# RFToy.net
KiCad netlist of a schematic drawn in EAGLE
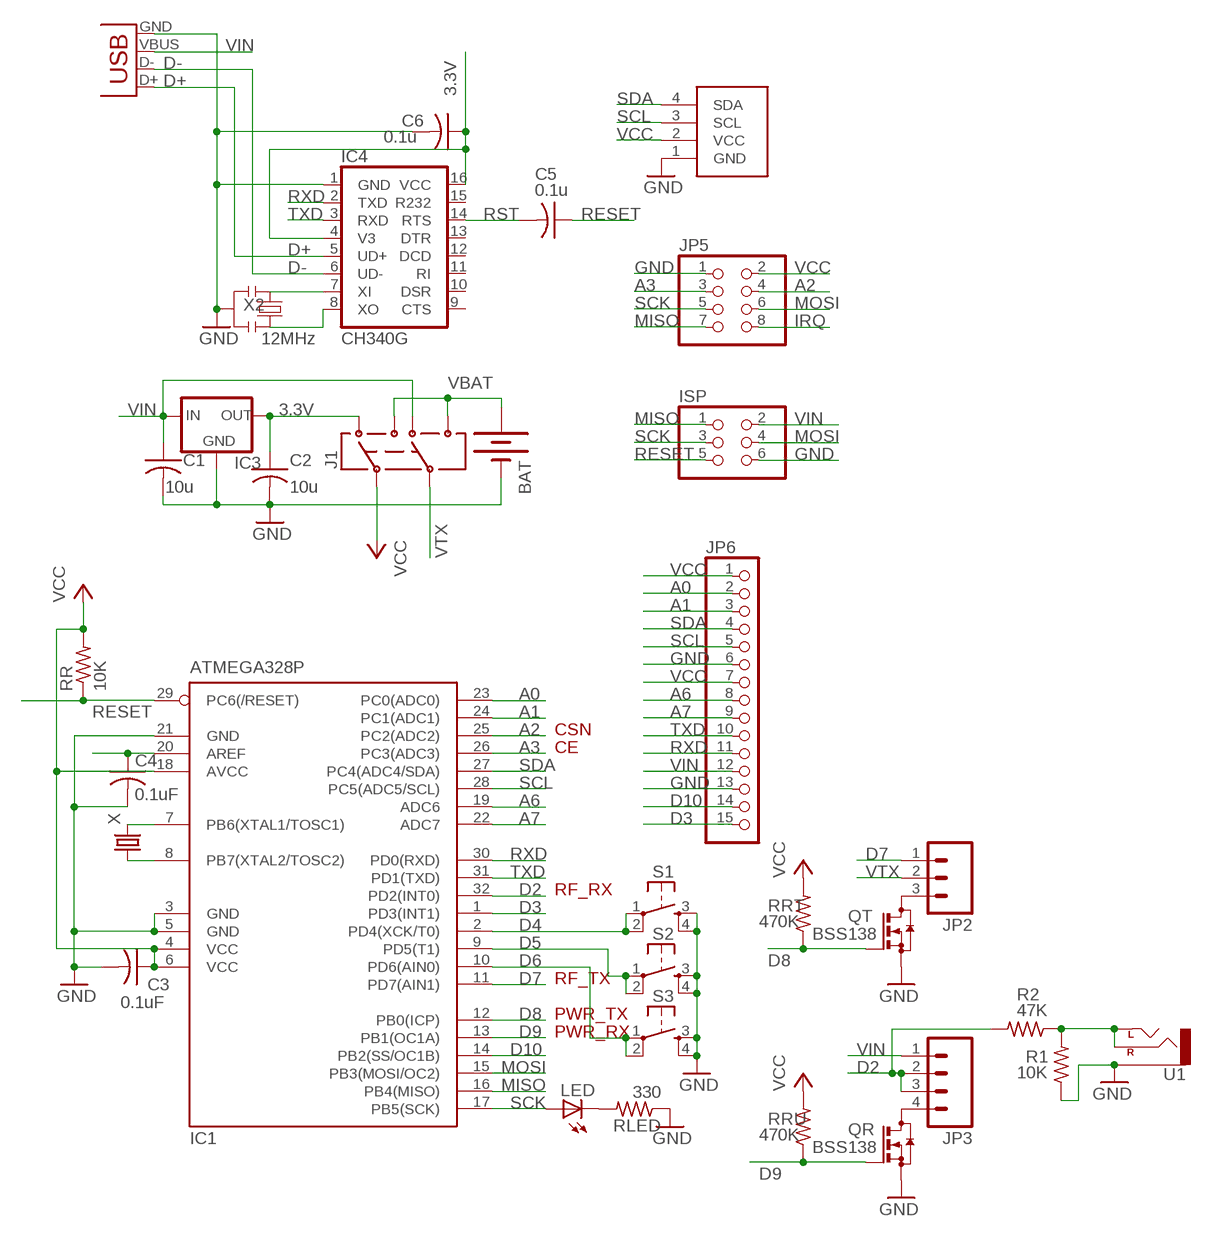
[diagram p0: schematic, sheet 1]

(export (version "E")
  (design (tool "Eeschema 10.0.6"))
  (components
    (comp (ref "BAT")
      (value "BATTERY20PTH")
      (footprint "eagle-import:BATTCOM_20MM_PTH")
      (libsource (lib "eagle-import") (part "BATTERY20PTH"))
    )
    (comp (ref "C1")
      (value "10u")
      (footprint "eagle-import:C0805K")
      (libsource (lib "eagle-import") (part "adafruit2013_C-USC0805K"))
    )
    (comp (ref "C2")
      (value "10u")
      (footprint "eagle-import:C0805K")
      (libsource (lib "eagle-import") (part "adafruit2013_C-USC0805K"))
    )
    (comp (ref "C3")
      (value "0.1uF")
      (footprint "eagle-import:C0805K")
      (libsource (lib "eagle-import") (part "adafruit2013_C-USC0805K"))
    )
    (comp (ref "C4")
      (value "0.1uF")
      (footprint "eagle-import:C0805K")
      (libsource (lib "eagle-import") (part "adafruit2013_C-USC0805K"))
    )
    (comp (ref "C5")
      (value "0.1u")
      (footprint "eagle-import:C0805K")
      (libsource (lib "eagle-import") (part "C-USC0805K"))
    )
    (comp (ref "C6")
      (value "0.1u")
      (footprint "eagle-import:C0805K")
      (libsource (lib "eagle-import") (part "C-USC0805K"))
    )
    (comp (ref "IC1")
      (value "ATMEGA328P")
      (footprint "eagle-import:TQFP32-08")
      (fields (field (name "MPN") "ATMEGA8-16AU"))
      (libsource (lib "eagle-import") (part "MEGA8-AI"))
    )
    (comp (ref "IC3")
      (value "MCP1700SOT233")
      (footprint "eagle-import:SOT23")
      (libsource (lib "eagle-import") (part "MCP1700SOT233"))
    )
    (comp (ref "IC4")
      (value "CH340G")
      (footprint "eagle-import:SO16")
      (libsource (lib "eagle-import") (part "CH340G"))
    )
    (comp (ref "ISP")
      (value "PINHD-2X3")
      (footprint "eagle-import:2X03")
      (libsource (lib "eagle-import") (part "PINHD-2X3"))
    )
    (comp (ref "J1")
      (value "AYZ0202")
      (footprint "eagle-import:AYZ0202")
      (libsource (lib "eagle-import") (part "AYZ0202"))
    )
    (comp (ref "JP2")
      (value "M03LOCK_LONGPADS")
      (footprint "eagle-import:1X03_LOCK_LONGPADS")
      (libsource (lib "eagle-import") (part "M03LOCK_LONGPADS"))
    )
    (comp (ref "JP3")
      (value "M04LOCK")
      (footprint "eagle-import:1X04_LOCK")
      (libsource (lib "eagle-import") (part "M04LOCK"))
    )
    (comp (ref "JP5")
      (value "PINHD-2X4")
      (footprint "eagle-import:2X04")
      (libsource (lib "eagle-import") (part "PINHD-2X4"))
    )
    (comp (ref "JP6")
      (value "PINHD-1X15-CB")
      (footprint "eagle-import:1X15-CB")
      (libsource (lib "eagle-import") (part "PINHD-1X15-CB"))
    )
    (comp (ref "LED")
      (value "LEDCHIPLED_0805")
      (footprint "eagle-import:CHIPLED_0805")
      (libsource (lib "eagle-import") (part "LEDCHIPLED_0805"))
    )
    (comp (ref "QR")
      (value "BSS138")
      (footprint "eagle-import:SOT23")
      (libsource (lib "eagle-import") (part "BSS123"))
    )
    (comp (ref "QT")
      (value "BSS138")
      (footprint "eagle-import:SOT23")
      (libsource (lib "eagle-import") (part "BSS123"))
    )
    (comp (ref "R1")
      (value "10K")
      (footprint "eagle-import:R0805")
      (libsource (lib "eagle-import") (part "R-US_R0805"))
    )
    (comp (ref "R2")
      (value "47K")
      (footprint "eagle-import:R0805")
      (libsource (lib "eagle-import") (part "R-US_R0805"))
    )
    (comp (ref "RLED")
      (value "330")
      (footprint "eagle-import:R0805")
      (libsource (lib "eagle-import") (part "R-US_R0805"))
    )
    (comp (ref "RR")
      (value "10K")
      (footprint "eagle-import:R0805")
      (libsource (lib "eagle-import") (part "R-US_R0805"))
    )
    (comp (ref "RRT")
      (value "470K")
      (footprint "eagle-import:R0805")
      (libsource (lib "eagle-import") (part "R-US_R0805"))
    )
    (comp (ref "RRU")
      (value "470K")
      (footprint "eagle-import:R0805")
      (libsource (lib "eagle-import") (part "R-US_R0805"))
    )
    (comp (ref "S1")
      (value "TAC_SWITCHPTH")
      (footprint "eagle-import:TACTILE-PTH")
      (libsource (lib "eagle-import") (part "TAC_SWITCHPTH"))
    )
    (comp (ref "S2")
      (value "TAC_SWITCHPTH")
      (footprint "eagle-import:TACTILE-PTH")
      (libsource (lib "eagle-import") (part "TAC_SWITCHPTH"))
    )
    (comp (ref "S3")
      (value "TAC_SWITCHPTH")
      (footprint "eagle-import:TACTILE-PTH")
      (libsource (lib "eagle-import") (part "TAC_SWITCHPTH"))
    )
    (comp (ref "U$1")
      (value "SSD1306_OLED_I2C")
      (footprint "eagle-import:SSD1306_OLED_I2C")
      (libsource (lib "eagle-import") (part "SSD1306_OLED_I2C"))
    )
    (comp (ref "U1")
      (value "AUDIO-JACKPTH")
      (footprint "eagle-import:AUDIO-JACK")
      (libsource (lib "eagle-import") (part "AUDIO-JACKPTH"))
    )
    (comp (ref "X")
      (value "CRYSTALTC26V")
      (footprint "eagle-import:TC26V")
      (libsource (lib "eagle-import") (part "CRYSTALTC26V"))
    )
    (comp (ref "X1")
      (value "USBSMD")
      (footprint "eagle-import:USB-MINIB")
      (libsource (lib "eagle-import") (part "USBSMD"))
    )
    (comp (ref "X2")
      (value "12MHz")
      (footprint "eagle-import:RESONATOR-SMD")
      (libsource (lib "eagle-import") (part "RESONATORSMD"))
    )
  )
  (nets
    (net (code "1") (name "/3.3V") (class "Default")
      (node (ref "C2") (pin "1") (pinfunction "1_1") (pintype "passive"))
      (node (ref "C6") (pin "1") (pinfunction "1_1") (pintype "passive"))
      (node (ref "IC3") (pin "2") (pinfunction "OUT_2") (pintype "passive"))
      (node (ref "IC4") (pin "16") (pinfunction "VCC_16") (pintype "power_in"))
      (node (ref "IC4") (pin "4") (pinfunction "V3_4") (pintype "bidirectional"))
      (node (ref "J1") (pin "3") (pinfunction "1_3") (pintype "bidirectional"))
    )
    (net (code "2") (name "/A0") (class "Default")
      (node (ref "IC1") (pin "23") (pinfunction "PC0(ADC0)_23") (pintype "bidirectional"))
      (node (ref "JP6") (pin "2") (pinfunction "2_2") (pintype "passive"))
    )
    (net (code "3") (name "/A1") (class "Default")
      (node (ref "IC1") (pin "24") (pinfunction "PC1(ADC1)_24") (pintype "bidirectional"))
      (node (ref "JP6") (pin "3") (pinfunction "3_3") (pintype "passive"))
    )
    (net (code "4") (name "/A2") (class "Default")
      (node (ref "IC1") (pin "25") (pinfunction "PC2(ADC2)_25") (pintype "bidirectional"))
      (node (ref "JP5") (pin "4") (pinfunction "4_4") (pintype "passive"))
    )
    (net (code "5") (name "/A3") (class "Default")
      (node (ref "IC1") (pin "26") (pinfunction "PC3(ADC3)_26") (pintype "bidirectional"))
      (node (ref "JP5") (pin "3") (pinfunction "3_3") (pintype "passive"))
    )
    (net (code "6") (name "/A6") (class "Default")
      (node (ref "IC1") (pin "19") (pinfunction "ADC6_19") (pintype "bidirectional"))
      (node (ref "JP6") (pin "8") (pinfunction "8_8") (pintype "passive"))
    )
    (net (code "7") (name "/A7") (class "Default")
      (node (ref "IC1") (pin "22") (pinfunction "ADC7_22") (pintype "bidirectional"))
      (node (ref "JP6") (pin "9") (pinfunction "9_9") (pintype "passive"))
    )
    (net (code "8") (name "/D+") (class "Default")
      (node (ref "IC4") (pin "5") (pinfunction "UD+_5") (pintype "bidirectional"))
      (node (ref "X1") (pin "D+") (pinfunction "D+_D+") (pintype "bidirectional"))
    )
    (net (code "9") (name "/D-") (class "Default")
      (node (ref "IC4") (pin "6") (pinfunction "UD-_6") (pintype "bidirectional"))
      (node (ref "X1") (pin "D-") (pinfunction "D-_D-") (pintype "bidirectional"))
    )
    (net (code "10") (name "/D2") (class "Default")
      (node (ref "IC1") (pin "32") (pinfunction "PD2(INT0)_32") (pintype "bidirectional"))
      (node (ref "JP3") (pin "2") (pinfunction "2_2") (pintype "passive"))
      (node (ref "JP3") (pin "3") (pinfunction "3_3") (pintype "passive"))
      (node (ref "R2") (pin "2") (pinfunction "2_2") (pintype "passive"))
    )
    (net (code "11") (name "/D3") (class "Default")
      (node (ref "IC1") (pin "1") (pinfunction "PD3(INT1)_1") (pintype "bidirectional"))
      (node (ref "JP6") (pin "15") (pinfunction "15_15") (pintype "passive"))
    )
    (net (code "12") (name "/D4") (class "Default")
      (node (ref "IC1") (pin "2") (pinfunction "PD4(XCK/T0)_2") (pintype "bidirectional"))
      (node (ref "S1") (pin "1") (pinfunction "1_1") (pintype "passive"))
      (node (ref "S1") (pin "2") (pinfunction "2_2") (pintype "passive"))
    )
    (net (code "13") (name "/D5") (class "Default")
      (node (ref "IC1") (pin "9") (pinfunction "PD5(T1)_9") (pintype "bidirectional"))
      (node (ref "S2") (pin "1") (pinfunction "1_1") (pintype "passive"))
      (node (ref "S2") (pin "2") (pinfunction "2_2") (pintype "passive"))
    )
    (net (code "14") (name "/D6") (class "Default")
      (node (ref "IC1") (pin "10") (pinfunction "PD6(AIN0)_10") (pintype "bidirectional"))
      (node (ref "S3") (pin "1") (pinfunction "1_1") (pintype "passive"))
      (node (ref "S3") (pin "2") (pinfunction "2_2") (pintype "passive"))
    )
    (net (code "15") (name "/D7") (class "Default")
      (node (ref "IC1") (pin "11") (pinfunction "PD7(AIN1)_11") (pintype "bidirectional"))
      (node (ref "JP2") (pin "1") (pinfunction "1_1") (pintype "passive"))
    )
    (net (code "16") (name "/D8") (class "Default")
      (node (ref "IC1") (pin "12") (pinfunction "PB0(ICP)_12") (pintype "bidirectional"))
      (node (ref "QT") (pin "1") (pinfunction "G_1") (pintype "passive"))
      (node (ref "RRT") (pin "1") (pinfunction "1_1") (pintype "passive"))
    )
    (net (code "17") (name "/D9") (class "Default")
      (node (ref "IC1") (pin "13") (pinfunction "PB1(OC1A)_13") (pintype "bidirectional"))
      (node (ref "QR") (pin "1") (pinfunction "G_1") (pintype "passive"))
      (node (ref "RRU") (pin "1") (pinfunction "1_1") (pintype "passive"))
    )
    (net (code "18") (name "/D10") (class "Default")
      (node (ref "IC1") (pin "14") (pinfunction "PB2(SS/OC1B)_14") (pintype "bidirectional"))
      (node (ref "JP6") (pin "14") (pinfunction "14_14") (pintype "passive"))
    )
    (net (code "19") (name "/IRQ") (class "Default")
      (node (ref "JP5") (pin "8") (pinfunction "8_8") (pintype "passive"))
    )
    (net (code "20") (name "/MISO") (class "Default")
      (node (ref "IC1") (pin "16") (pinfunction "PB4(MISO)_16") (pintype "bidirectional"))
      (node (ref "ISP") (pin "1") (pinfunction "1_1") (pintype "passive"))
      (node (ref "JP5") (pin "7") (pinfunction "7_7") (pintype "passive"))
    )
    (net (code "21") (name "/MOSI") (class "Default")
      (node (ref "IC1") (pin "15") (pinfunction "PB3(MOSI/OC2)_15") (pintype "bidirectional"))
      (node (ref "ISP") (pin "4") (pinfunction "4_4") (pintype "passive"))
      (node (ref "JP5") (pin "6") (pinfunction "6_6") (pintype "passive"))
    )
    (net (code "22") (name "/RESET") (class "Default")
      (node (ref "C5") (pin "1") (pinfunction "1_1") (pintype "passive"))
      (node (ref "IC1") (pin "29") (pinfunction "PC6(/RESET)_29") (pintype "bidirectional"))
      (node (ref "ISP") (pin "5") (pinfunction "5_5") (pintype "passive"))
      (node (ref "RR") (pin "1") (pinfunction "1_1") (pintype "passive"))
    )
    (net (code "23") (name "/RST") (class "Default")
      (node (ref "C5") (pin "2") (pinfunction "2_2") (pintype "passive"))
      (node (ref "IC4") (pin "14") (pinfunction "RTS_14") (pintype "bidirectional"))
    )
    (net (code "24") (name "/RXD") (class "Default")
      (node (ref "IC1") (pin "30") (pinfunction "PD0(RXD)_30") (pintype "bidirectional"))
      (node (ref "IC4") (pin "2") (pinfunction "TXD_2") (pintype "bidirectional"))
      (node (ref "JP6") (pin "11") (pinfunction "11_11") (pintype "passive"))
    )
    (net (code "25") (name "/SCK") (class "Default")
      (node (ref "IC1") (pin "17") (pinfunction "PB5(SCK)_17") (pintype "bidirectional"))
      (node (ref "ISP") (pin "3") (pinfunction "3_3") (pintype "passive"))
      (node (ref "JP5") (pin "5") (pinfunction "5_5") (pintype "passive"))
      (node (ref "LED") (pin "A") (pinfunction "A_A") (pintype "passive"))
    )
    (net (code "26") (name "/SCL") (class "Default")
      (node (ref "IC1") (pin "28") (pinfunction "PC5(ADC5/SCL)_28") (pintype "bidirectional"))
      (node (ref "JP6") (pin "5") (pinfunction "5_5") (pintype "passive"))
      (node (ref "U$1") (pin "3") (pinfunction "SCL_3") (pintype "bidirectional"))
    )
    (net (code "27") (name "/SDA") (class "Default")
      (node (ref "IC1") (pin "27") (pinfunction "PC4(ADC4/SDA)_27") (pintype "bidirectional"))
      (node (ref "JP6") (pin "4") (pinfunction "4_4") (pintype "passive"))
      (node (ref "U$1") (pin "4") (pinfunction "SDA_4") (pintype "bidirectional"))
    )
    (net (code "28") (name "/TXD") (class "Default")
      (node (ref "IC1") (pin "31") (pinfunction "PD1(TXD)_31") (pintype "bidirectional"))
      (node (ref "IC4") (pin "3") (pinfunction "RXD_3") (pintype "bidirectional"))
      (node (ref "JP6") (pin "10") (pinfunction "10_10") (pintype "passive"))
    )
    (net (code "29") (name "/VBAT") (class "Default")
      (node (ref "BAT") (pin "1") (pinfunction "+_1") (pintype "power_in"))
      (node (ref "J1") (pin "1") (pinfunction "3_1") (pintype "bidirectional"))
      (node (ref "J1") (pin "4") (pinfunction "6_4") (pintype "bidirectional"))
    )
    (net (code "30") (name "/VIN") (class "Default")
      (node (ref "C1") (pin "1") (pinfunction "1_1") (pintype "passive"))
      (node (ref "IC3") (pin "3") (pinfunction "IN_3") (pintype "input"))
      (node (ref "ISP") (pin "2") (pinfunction "2_2") (pintype "passive"))
      (node (ref "J1") (pin "6") (pinfunction "4_6") (pintype "bidirectional"))
      (node (ref "JP3") (pin "1") (pinfunction "1_1") (pintype "passive"))
      (node (ref "JP6") (pin "12") (pinfunction "12_12") (pintype "passive"))
      (node (ref "X1") (pin "VBUS") (pinfunction "VBUS_VBUS") (pintype "bidirectional"))
    )
    (net (code "31") (name "/VTX") (class "Default")
      (node (ref "J1") (pin "5") (pinfunction "5_5") (pintype "bidirectional"))
      (node (ref "JP2") (pin "2") (pinfunction "2_2") (pintype "passive"))
    )
    (net (code "32") (name "GND") (class "Default")
      (node (ref "BAT") (pin "2") (pinfunction "-_2") (pintype "power_in"))
      (node (ref "C1") (pin "2") (pinfunction "2_2") (pintype "passive"))
      (node (ref "C2") (pin "2") (pinfunction "2_2") (pintype "passive"))
      (node (ref "C3") (pin "2") (pinfunction "2_2") (pintype "passive"))
      (node (ref "C4") (pin "2") (pinfunction "2_2") (pintype "passive"))
      (node (ref "C6") (pin "2") (pinfunction "2_2") (pintype "passive"))
      (node (ref "IC1") (pin "21") (pinfunction "GND_21") (pintype "power_in"))
      (node (ref "IC1") (pin "3") (pinfunction "GND_3") (pintype "power_in"))
      (node (ref "IC1") (pin "5") (pinfunction "GND_5") (pintype "power_in"))
      (node (ref "IC3") (pin "1") (pinfunction "GND_1") (pintype "input"))
      (node (ref "IC4") (pin "1") (pinfunction "GND_1") (pintype "power_in"))
      (node (ref "ISP") (pin "6") (pinfunction "6_6") (pintype "passive"))
      (node (ref "JP5") (pin "1") (pinfunction "1_1") (pintype "passive"))
      (node (ref "JP6") (pin "13") (pinfunction "13_13") (pintype "passive"))
      (node (ref "JP6") (pin "6") (pinfunction "6_6") (pintype "passive"))
      (node (ref "QR") (pin "2") (pinfunction "S_2") (pintype "passive"))
      (node (ref "QT") (pin "2") (pinfunction "S_2") (pintype "passive"))
      (node (ref "R1") (pin "1") (pinfunction "1_1") (pintype "passive"))
      (node (ref "RLED") (pin "1") (pinfunction "1_1") (pintype "passive"))
      (node (ref "S1") (pin "3") (pinfunction "3_3") (pintype "passive"))
      (node (ref "S1") (pin "4") (pinfunction "4_4") (pintype "passive"))
      (node (ref "S2") (pin "3") (pinfunction "3_3") (pintype "passive"))
      (node (ref "S2") (pin "4") (pinfunction "4_4") (pintype "passive"))
      (node (ref "S3") (pin "3") (pinfunction "3_3") (pintype "passive"))
      (node (ref "S3") (pin "4") (pinfunction "4_4") (pintype "passive"))
      (node (ref "U$1") (pin "1") (pinfunction "GND_1") (pintype "power_in"))
      (node (ref "U1") (pin "SLEEVE") (pinfunction "SLEEVE_SLEEVE") (pintype "bidirectional"))
      (node (ref "X1") (pin "GND") (pinfunction "GND_GND") (pintype "bidirectional"))
      (node (ref "X2") (pin "2") (pinfunction "2_2") (pintype "passive"))
    )
    (net (code "33") (name "Net-(IC1-AREF)") (class "Default")
      (node (ref "C4") (pin "1") (pinfunction "1_1") (pintype "passive"))
      (node (ref "IC1") (pin "20") (pinfunction "AREF_20") (pintype "passive"))
    )
    (net (code "34") (name "Net-(IC1-PB6(XTAL1{slash}TOSC1))") (class "Default")
      (node (ref "IC1") (pin "7") (pinfunction "PB6(XTAL1/TOSC1)_7") (pintype "bidirectional"))
      (node (ref "X") (pin "2") (pinfunction "2_2") (pintype "passive"))
    )
    (net (code "35") (name "Net-(IC1-PB7(XTAL2{slash}TOSC2))") (class "Default")
      (node (ref "IC1") (pin "8") (pinfunction "PB7(XTAL2/TOSC2)_8") (pintype "bidirectional"))
      (node (ref "X") (pin "1") (pinfunction "1_1") (pintype "passive"))
    )
    (net (code "36") (name "Net-(IC4-XI)") (class "Default")
      (node (ref "IC4") (pin "7") (pinfunction "XI_7") (pintype "bidirectional"))
      (node (ref "X2") (pin "1") (pinfunction "1_1") (pintype "passive"))
    )
    (net (code "37") (name "Net-(IC4-XO)") (class "Default")
      (node (ref "IC4") (pin "8") (pinfunction "XO_8") (pintype "bidirectional"))
      (node (ref "X2") (pin "3") (pinfunction "3_3") (pintype "passive"))
    )
    (net (code "38") (name "Net-(LED-PadC)") (class "Default")
      (node (ref "LED") (pin "C") (pinfunction "C_C") (pintype "passive"))
      (node (ref "RLED") (pin "2") (pinfunction "2_2") (pintype "passive"))
    )
    (net (code "39") (name "Net-(QR-D)") (class "Default")
      (node (ref "JP3") (pin "4") (pinfunction "4_4") (pintype "passive"))
      (node (ref "QR") (pin "3") (pinfunction "D_3") (pintype "passive"))
    )
    (net (code "40") (name "Net-(QT-D)") (class "Default")
      (node (ref "JP2") (pin "3") (pinfunction "3_3") (pintype "passive"))
      (node (ref "QT") (pin "3") (pinfunction "D_3") (pintype "passive"))
    )
    (net (code "41") (name "Net-(U1-LEFT)") (class "Default")
      (node (ref "R1") (pin "2") (pinfunction "2_2") (pintype "passive"))
      (node (ref "R2") (pin "1") (pinfunction "1_1") (pintype "passive"))
      (node (ref "U1") (pin "RING") (pinfunction "RIGHT_RING") (pintype "bidirectional"))
      (node (ref "U1") (pin "TIP") (pinfunction "LEFT_TIP") (pintype "bidirectional"))
    )
    (net (code "42") (name "VCC") (class "Default")
      (node (ref "C3") (pin "1") (pinfunction "1_1") (pintype "passive"))
      (node (ref "IC1") (pin "18") (pinfunction "AVCC_18") (pintype "power_in"))
      (node (ref "IC1") (pin "4") (pinfunction "VCC_4") (pintype "power_in"))
      (node (ref "IC1") (pin "6") (pinfunction "VCC_6") (pintype "power_in"))
      (node (ref "J1") (pin "2") (pinfunction "2_2") (pintype "bidirectional"))
      (node (ref "JP5") (pin "2") (pinfunction "2_2") (pintype "passive"))
      (node (ref "JP6") (pin "1") (pinfunction "1_1") (pintype "passive"))
      (node (ref "JP6") (pin "7") (pinfunction "7_7") (pintype "passive"))
      (node (ref "RR") (pin "2") (pinfunction "2_2") (pintype "passive"))
      (node (ref "RRT") (pin "2") (pinfunction "2_2") (pintype "passive"))
      (node (ref "RRU") (pin "2") (pinfunction "2_2") (pintype "passive"))
      (node (ref "U$1") (pin "2") (pinfunction "VCC_2") (pintype "power_in"))
    )
    (net (code "43") (name "unconnected-(IC4-CTS-Pad9)") (class "Default")
      (node (ref "IC4") (pin "9") (pinfunction "CTS_9") (pintype "bidirectional"))
    )
    (net (code "44") (name "unconnected-(IC4-DCD-Pad12)") (class "Default")
      (node (ref "IC4") (pin "12") (pinfunction "DCD_12") (pintype "bidirectional"))
    )
    (net (code "45") (name "unconnected-(IC4-DSR-Pad10)") (class "Default")
      (node (ref "IC4") (pin "10") (pinfunction "DSR_10") (pintype "bidirectional"))
    )
    (net (code "46") (name "unconnected-(IC4-DTR-Pad13)") (class "Default")
      (node (ref "IC4") (pin "13") (pinfunction "DTR_13") (pintype "bidirectional"))
    )
    (net (code "47") (name "unconnected-(IC4-R232-Pad15)") (class "Default")
      (node (ref "IC4") (pin "15") (pinfunction "R232_15") (pintype "bidirectional"))
    )
    (net (code "48") (name "unconnected-(IC4-RI-Pad11)") (class "Default")
      (node (ref "IC4") (pin "11") (pinfunction "RI_11") (pintype "bidirectional"))
    )
  )
)
